# inverter.net
KiCad netlist of a schematic drawn in EAGLE
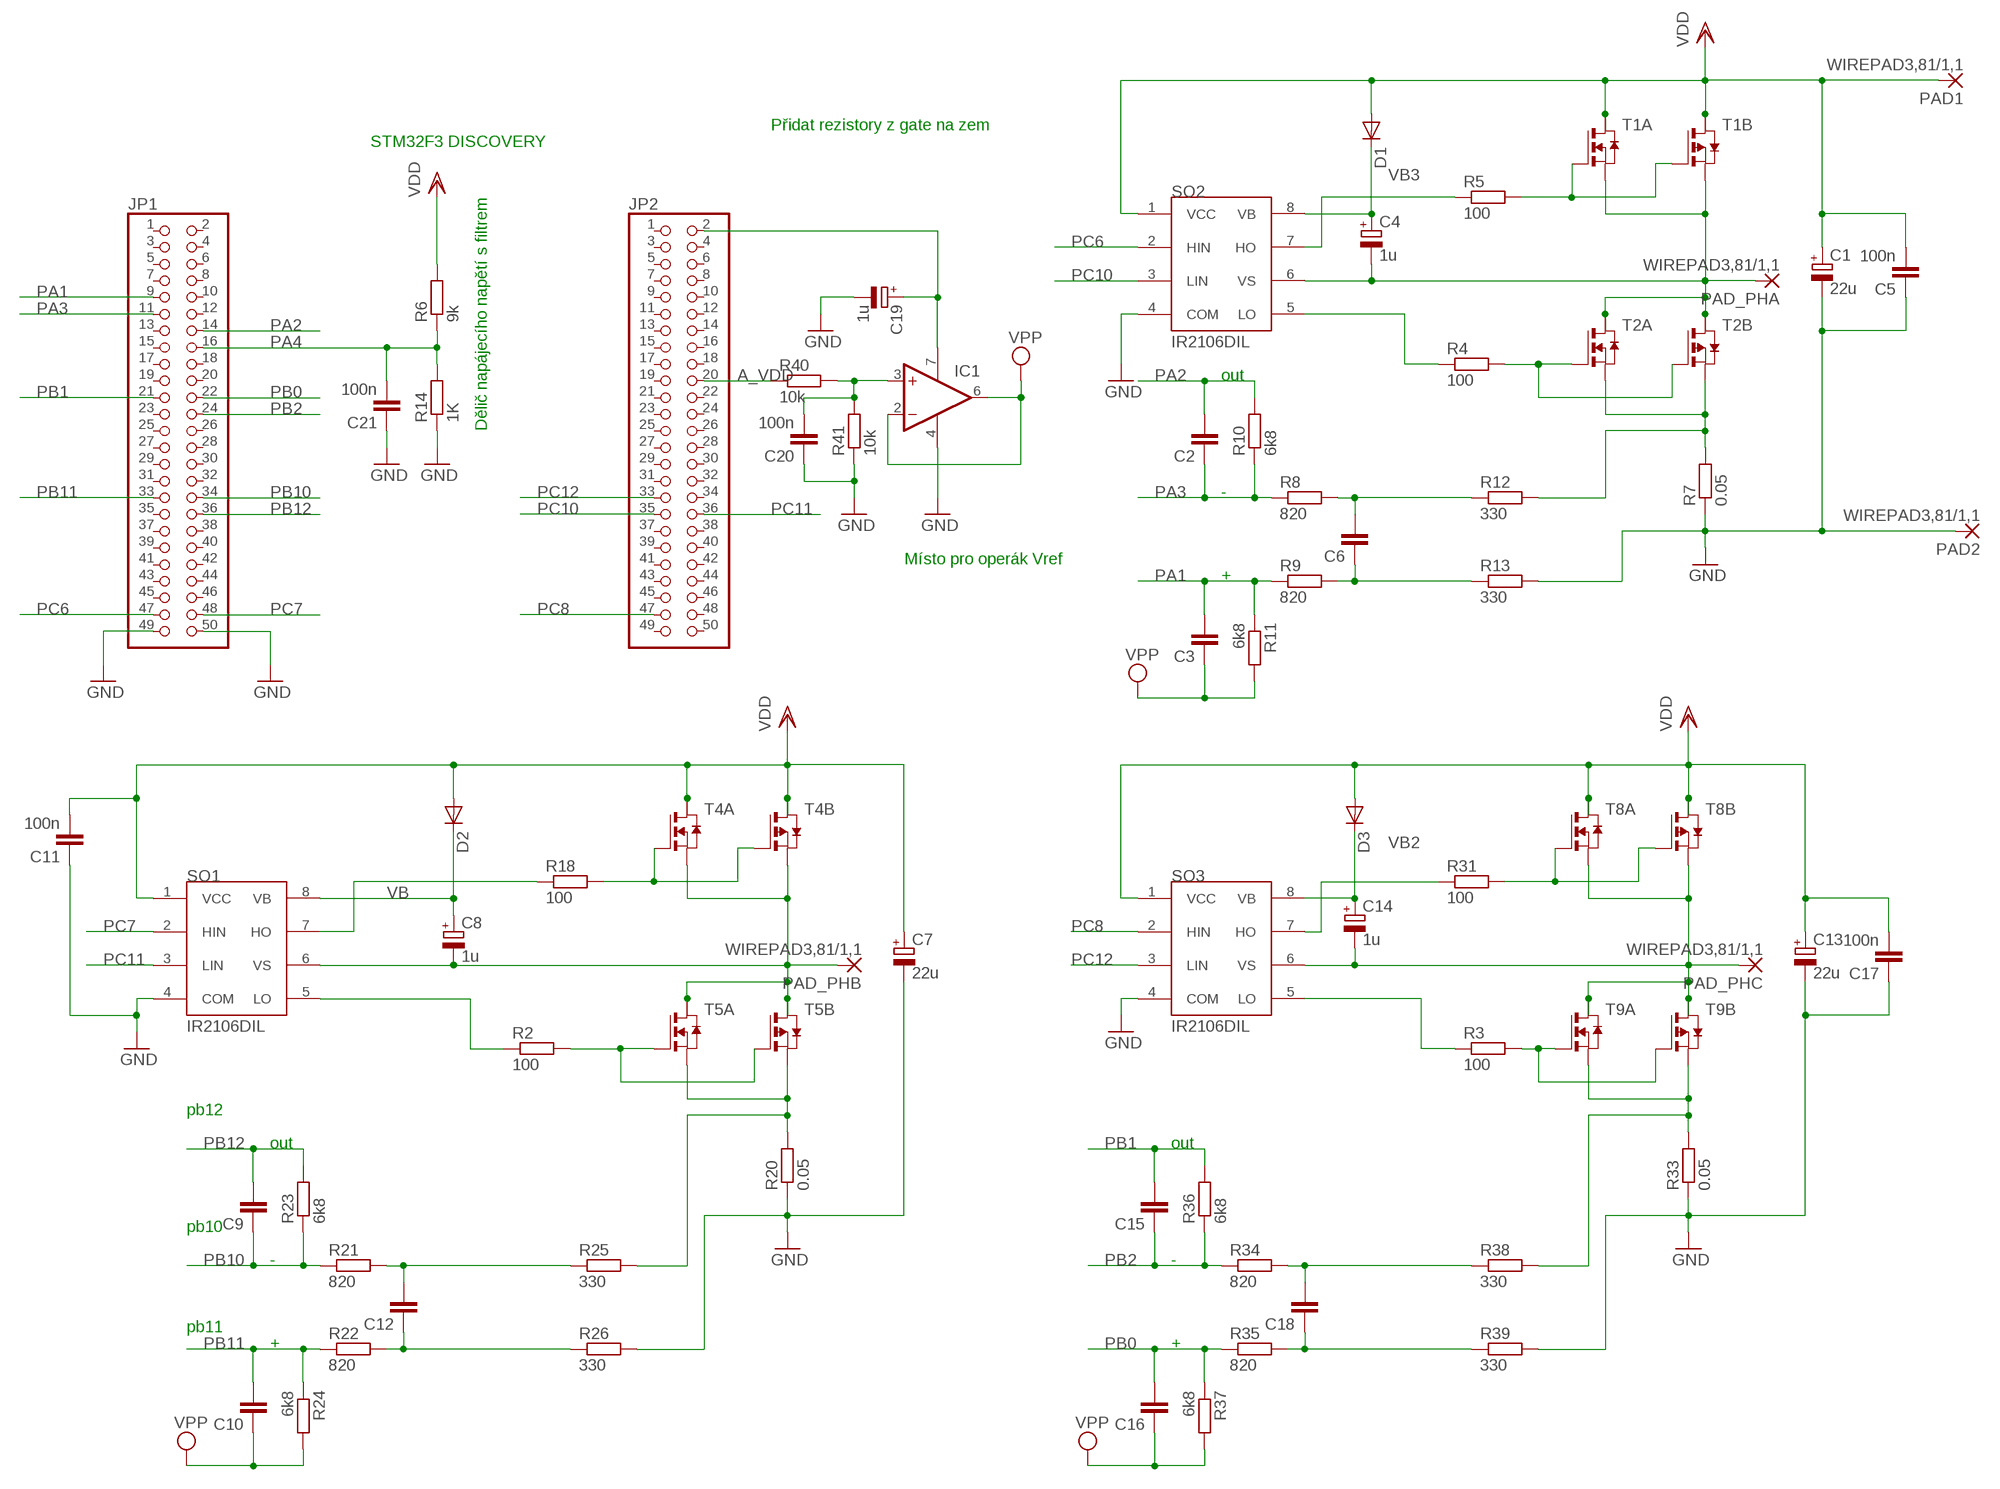
[diagram p0: schematic, sheet 1]

(export (version "E")
  (design (tool "Eeschema 10.0.6"))
  (components
    (comp (ref "C1")
      (value "22u")
      (footprint "eagle-import:SMC_C")
      (libsource (lib "eagle-import") (part "CPOL-EUSMCC"))
    )
    (comp (ref "C2")
      (value "C-EUC0805")
      (footprint "eagle-import:C0805")
      (libsource (lib "eagle-import") (part "C-EUC0805"))
    )
    (comp (ref "C3")
      (value "C-EUC0805")
      (footprint "eagle-import:C0805")
      (libsource (lib "eagle-import") (part "C-EUC0805"))
    )
    (comp (ref "C4")
      (value "1u")
      (footprint "eagle-import:SMC_P")
      (libsource (lib "eagle-import") (part "CPOL-EUSMCP"))
    )
    (comp (ref "C5")
      (value "100n")
      (footprint "eagle-import:C0805")
      (libsource (lib "eagle-import") (part "C-EUC0805"))
    )
    (comp (ref "C6")
      (value "C-EUC0805")
      (footprint "eagle-import:C0805")
      (libsource (lib "eagle-import") (part "C-EUC0805"))
    )
    (comp (ref "C7")
      (value "22u")
      (footprint "eagle-import:SMC_C")
      (libsource (lib "eagle-import") (part "CPOL-EUSMCC"))
    )
    (comp (ref "C8")
      (value "1u")
      (footprint "eagle-import:SMC_P")
      (libsource (lib "eagle-import") (part "CPOL-EUSMCP"))
    )
    (comp (ref "C9")
      (value "C-EUC0805")
      (footprint "eagle-import:C0805")
      (libsource (lib "eagle-import") (part "C-EUC0805"))
    )
    (comp (ref "C10")
      (value "C-EUC0805")
      (footprint "eagle-import:C0805")
      (libsource (lib "eagle-import") (part "C-EUC0805"))
    )
    (comp (ref "C11")
      (value "100n")
      (footprint "eagle-import:C0805")
      (libsource (lib "eagle-import") (part "C-EUC0805"))
    )
    (comp (ref "C12")
      (value "C-EUC0805")
      (footprint "eagle-import:C0805")
      (libsource (lib "eagle-import") (part "C-EUC0805"))
    )
    (comp (ref "C13")
      (value "22u")
      (footprint "eagle-import:SMC_C")
      (libsource (lib "eagle-import") (part "CPOL-EUSMCC"))
    )
    (comp (ref "C14")
      (value "1u")
      (footprint "eagle-import:SMC_P")
      (libsource (lib "eagle-import") (part "CPOL-EUSMCP"))
    )
    (comp (ref "C15")
      (value "C-EUC0805")
      (footprint "eagle-import:C0805")
      (libsource (lib "eagle-import") (part "C-EUC0805"))
    )
    (comp (ref "C16")
      (value "C-EUC0805")
      (footprint "eagle-import:C0805")
      (libsource (lib "eagle-import") (part "C-EUC0805"))
    )
    (comp (ref "C17")
      (value "100n")
      (footprint "eagle-import:C0805")
      (libsource (lib "eagle-import") (part "C-EUC0805"))
    )
    (comp (ref "C18")
      (value "C-EUC0805")
      (footprint "eagle-import:C0805")
      (libsource (lib "eagle-import") (part "C-EUC0805"))
    )
    (comp (ref "C19")
      (value "1u")
      (footprint "eagle-import:SMC_P")
      (libsource (lib "eagle-import") (part "CPOL-EUSMCP"))
    )
    (comp (ref "C20")
      (value "100n")
      (footprint "eagle-import:C0805")
      (libsource (lib "eagle-import") (part "C-EUC0805"))
    )
    (comp (ref "C21")
      (value "100n")
      (footprint "eagle-import:C0805")
      (libsource (lib "eagle-import") (part "C-EUC0805"))
    )
    (comp (ref "D1")
      (value "DIODE-DO214AC")
      (footprint "eagle-import:DO214AC")
      (libsource (lib "eagle-import") (part "DIODE-DO214AC"))
    )
    (comp (ref "D2")
      (value "DIODE-DO214AC")
      (footprint "eagle-import:DO214AC")
      (libsource (lib "eagle-import") (part "DIODE-DO214AC"))
    )
    (comp (ref "D3")
      (value "DIODE-DO214AC")
      (footprint "eagle-import:DO214AC")
      (libsource (lib "eagle-import") (part "DIODE-DO214AC"))
    )
    (comp (ref "IC1")
      (value "1AMP_P7+4D")
      (footprint "eagle-import:SO08")
      (libsource (lib "eagle-import") (part "1AMP_P7+4D"))
    )
    (comp (ref "JP1")
      (value "PINHD-2X25")
      (footprint "eagle-import:2X25")
      (libsource (lib "eagle-import") (part "PINHD-2X25"))
    )
    (comp (ref "JP2")
      (value "PINHD-2X25")
      (footprint "eagle-import:2X25")
      (libsource (lib "eagle-import") (part "PINHD-2X25"))
    )
    (comp (ref "PAD1")
      (value "WIREPAD3,81/1,1")
      (footprint "eagle-import:3,81_1,1")
      (libsource (lib "eagle-import") (part "WIREPAD3,81/1,1"))
    )
    (comp (ref "PAD2")
      (value "WIREPAD3,81/1,1")
      (footprint "eagle-import:3,81_1,1")
      (libsource (lib "eagle-import") (part "WIREPAD3,81/1,1"))
    )
    (comp (ref "PAD_PHA")
      (value "WIREPAD3,81/1,1")
      (footprint "eagle-import:3,81_1,1")
      (libsource (lib "eagle-import") (part "WIREPAD3,81/1,1"))
    )
    (comp (ref "PAD_PHB")
      (value "WIREPAD3,81/1,1")
      (footprint "eagle-import:3,81_1,1")
      (libsource (lib "eagle-import") (part "WIREPAD3,81/1,1"))
    )
    (comp (ref "PAD_PHC")
      (value "WIREPAD3,81/1,1")
      (footprint "eagle-import:3,81_1,1")
      (libsource (lib "eagle-import") (part "WIREPAD3,81/1,1"))
    )
    (comp (ref "R2")
      (value "100")
      (footprint "eagle-import:M1206")
      (libsource (lib "eagle-import") (part "R-EU_M1206"))
    )
    (comp (ref "R3")
      (value "100")
      (footprint "eagle-import:M1206")
      (libsource (lib "eagle-import") (part "R-EU_M1206"))
    )
    (comp (ref "R4")
      (value "100")
      (footprint "eagle-import:M1206")
      (libsource (lib "eagle-import") (part "R-EU_M1206"))
    )
    (comp (ref "R5")
      (value "100")
      (footprint "eagle-import:M1206")
      (libsource (lib "eagle-import") (part "R-EU_M1206"))
    )
    (comp (ref "R6")
      (value "9k")
      (footprint "eagle-import:M1206")
      (libsource (lib "eagle-import") (part "R-EU_M1206"))
    )
    (comp (ref "R7")
      (value "0.05")
      (footprint "eagle-import:R2512")
      (libsource (lib "eagle-import") (part "R-EU_R2512"))
    )
    (comp (ref "R8")
      (value "820")
      (footprint "eagle-import:M1206")
      (libsource (lib "eagle-import") (part "R-EU_M1206"))
    )
    (comp (ref "R9")
      (value "820")
      (footprint "eagle-import:M1206")
      (libsource (lib "eagle-import") (part "R-EU_M1206"))
    )
    (comp (ref "R10")
      (value "6k8")
      (footprint "eagle-import:M1206")
      (libsource (lib "eagle-import") (part "R-EU_M1206"))
    )
    (comp (ref "R11")
      (value "6k8")
      (footprint "eagle-import:M1206")
      (libsource (lib "eagle-import") (part "R-EU_M1206"))
    )
    (comp (ref "R12")
      (value "330")
      (footprint "eagle-import:M1206")
      (libsource (lib "eagle-import") (part "R-EU_M1206"))
    )
    (comp (ref "R13")
      (value "330")
      (footprint "eagle-import:M1206")
      (libsource (lib "eagle-import") (part "R-EU_M1206"))
    )
    (comp (ref "R14")
      (value "1K")
      (footprint "eagle-import:M1206")
      (libsource (lib "eagle-import") (part "R-EU_M1206"))
    )
    (comp (ref "R18")
      (value "100")
      (footprint "eagle-import:M1206")
      (libsource (lib "eagle-import") (part "R-EU_M1206"))
    )
    (comp (ref "R20")
      (value "0.05")
      (footprint "eagle-import:R2512")
      (libsource (lib "eagle-import") (part "R-EU_R2512"))
    )
    (comp (ref "R21")
      (value "820")
      (footprint "eagle-import:M1206")
      (libsource (lib "eagle-import") (part "R-EU_M1206"))
    )
    (comp (ref "R22")
      (value "820")
      (footprint "eagle-import:M1206")
      (libsource (lib "eagle-import") (part "R-EU_M1206"))
    )
    (comp (ref "R23")
      (value "6k8")
      (footprint "eagle-import:M1206")
      (libsource (lib "eagle-import") (part "R-EU_M1206"))
    )
    (comp (ref "R24")
      (value "6k8")
      (footprint "eagle-import:M1206")
      (libsource (lib "eagle-import") (part "R-EU_M1206"))
    )
    (comp (ref "R25")
      (value "330")
      (footprint "eagle-import:M1206")
      (libsource (lib "eagle-import") (part "R-EU_M1206"))
    )
    (comp (ref "R26")
      (value "330")
      (footprint "eagle-import:M1206")
      (libsource (lib "eagle-import") (part "R-EU_M1206"))
    )
    (comp (ref "R31")
      (value "100")
      (footprint "eagle-import:M1206")
      (libsource (lib "eagle-import") (part "R-EU_M1206"))
    )
    (comp (ref "R33")
      (value "0.05")
      (footprint "eagle-import:R2512")
      (libsource (lib "eagle-import") (part "R-EU_R2512"))
    )
    (comp (ref "R34")
      (value "820")
      (footprint "eagle-import:M1206")
      (libsource (lib "eagle-import") (part "R-EU_M1206"))
    )
    (comp (ref "R35")
      (value "820")
      (footprint "eagle-import:M1206")
      (libsource (lib "eagle-import") (part "R-EU_M1206"))
    )
    (comp (ref "R36")
      (value "6k8")
      (footprint "eagle-import:M1206")
      (libsource (lib "eagle-import") (part "R-EU_M1206"))
    )
    (comp (ref "R37")
      (value "6k8")
      (footprint "eagle-import:M1206")
      (libsource (lib "eagle-import") (part "R-EU_M1206"))
    )
    (comp (ref "R38")
      (value "330")
      (footprint "eagle-import:M1206")
      (libsource (lib "eagle-import") (part "R-EU_M1206"))
    )
    (comp (ref "R39")
      (value "330")
      (footprint "eagle-import:M1206")
      (libsource (lib "eagle-import") (part "R-EU_M1206"))
    )
    (comp (ref "R40")
      (value "10k")
      (footprint "eagle-import:M1206")
      (libsource (lib "eagle-import") (part "R-EU_M1206"))
    )
    (comp (ref "R41")
      (value "10k")
      (footprint "eagle-import:M1206")
      (libsource (lib "eagle-import") (part "R-EU_M1206"))
    )
    (comp (ref "SO1")
      (value "IR2106DIL")
      (footprint "eagle-import:SO8")
      (libsource (lib "eagle-import") (part "IR2106DIL"))
    )
    (comp (ref "SO2")
      (value "IR2106DIL")
      (footprint "eagle-import:SO8")
      (libsource (lib "eagle-import") (part "IR2106DIL"))
    )
    (comp (ref "SO3")
      (value "IR2106DIL")
      (footprint "eagle-import:SO8")
      (libsource (lib "eagle-import") (part "IR2106DIL"))
    )
    (comp (ref "T1")
      (value "PN_MOSFET-SO8")
      (footprint "eagle-import:SO8")
      (libsource (lib "eagle-import") (part "PN_MOSFET-SO8"))
    )
    (comp (ref "T2")
      (value "PN_MOSFET-SO8")
      (footprint "eagle-import:SO8")
      (libsource (lib "eagle-import") (part "PN_MOSFET-SO8"))
    )
    (comp (ref "T4")
      (value "PN_MOSFET-SO8")
      (footprint "eagle-import:SO8")
      (libsource (lib "eagle-import") (part "PN_MOSFET-SO8"))
    )
    (comp (ref "T5")
      (value "PN_MOSFET-SO8")
      (footprint "eagle-import:SO8")
      (libsource (lib "eagle-import") (part "PN_MOSFET-SO8"))
    )
    (comp (ref "T8")
      (value "PN_MOSFET-SO8")
      (footprint "eagle-import:SO8")
      (libsource (lib "eagle-import") (part "PN_MOSFET-SO8"))
    )
    (comp (ref "T9")
      (value "PN_MOSFET-SO8")
      (footprint "eagle-import:SO8")
      (libsource (lib "eagle-import") (part "PN_MOSFET-SO8"))
    )
  )
  (nets
    (net (code "1") (name "/A_VDD") (class "Default")
      (node (ref "JP2") (pin "20") (pinfunction "20_20") (pintype "passive"))
      (node (ref "R40") (pin "1") (pinfunction "1_1") (pintype "passive"))
    )
    (net (code "2") (name "/PA1") (class "Default")
      (node (ref "C3") (pin "2") (pinfunction "2_2") (pintype "passive"))
      (node (ref "JP1") (pin "9") (pinfunction "9_9") (pintype "passive"))
      (node (ref "R11") (pin "1") (pinfunction "1_1") (pintype "passive"))
      (node (ref "R9") (pin "1") (pinfunction "1_1") (pintype "passive"))
    )
    (net (code "3") (name "/PA2") (class "Default")
      (node (ref "C2") (pin "2") (pinfunction "2_2") (pintype "passive"))
      (node (ref "JP1") (pin "14") (pinfunction "14_14") (pintype "passive"))
      (node (ref "R10") (pin "2") (pinfunction "2_2") (pintype "passive"))
    )
    (net (code "4") (name "/PA3") (class "Default")
      (node (ref "C2") (pin "1") (pinfunction "1_1") (pintype "passive"))
      (node (ref "JP1") (pin "11") (pinfunction "11_11") (pintype "passive"))
      (node (ref "R10") (pin "1") (pinfunction "1_1") (pintype "passive"))
      (node (ref "R8") (pin "1") (pinfunction "1_1") (pintype "passive"))
    )
    (net (code "5") (name "/PA4") (class "Default")
      (node (ref "C21") (pin "2") (pinfunction "2_2") (pintype "passive"))
      (node (ref "JP1") (pin "16") (pinfunction "16_16") (pintype "passive"))
      (node (ref "R14") (pin "2") (pinfunction "2_2") (pintype "passive"))
      (node (ref "R6") (pin "1") (pinfunction "1_1") (pintype "passive"))
    )
    (net (code "6") (name "/PB0") (class "Default")
      (node (ref "C16") (pin "2") (pinfunction "2_2") (pintype "passive"))
      (node (ref "JP1") (pin "22") (pinfunction "22_22") (pintype "passive"))
      (node (ref "R35") (pin "1") (pinfunction "1_1") (pintype "passive"))
      (node (ref "R37") (pin "1") (pinfunction "1_1") (pintype "passive"))
    )
    (net (code "7") (name "/PB1") (class "Default")
      (node (ref "C15") (pin "2") (pinfunction "2_2") (pintype "passive"))
      (node (ref "JP1") (pin "21") (pinfunction "21_21") (pintype "passive"))
      (node (ref "R36") (pin "2") (pinfunction "2_2") (pintype "passive"))
    )
    (net (code "8") (name "/PB2") (class "Default")
      (node (ref "C15") (pin "1") (pinfunction "1_1") (pintype "passive"))
      (node (ref "JP1") (pin "24") (pinfunction "24_24") (pintype "passive"))
      (node (ref "R34") (pin "1") (pinfunction "1_1") (pintype "passive"))
      (node (ref "R36") (pin "1") (pinfunction "1_1") (pintype "passive"))
    )
    (net (code "9") (name "/PB10") (class "Default")
      (node (ref "C9") (pin "1") (pinfunction "1_1") (pintype "passive"))
      (node (ref "JP1") (pin "34") (pinfunction "34_34") (pintype "passive"))
      (node (ref "R21") (pin "1") (pinfunction "1_1") (pintype "passive"))
      (node (ref "R23") (pin "1") (pinfunction "1_1") (pintype "passive"))
    )
    (net (code "10") (name "/PB11") (class "Default")
      (node (ref "C10") (pin "2") (pinfunction "2_2") (pintype "passive"))
      (node (ref "JP1") (pin "33") (pinfunction "33_33") (pintype "passive"))
      (node (ref "R22") (pin "1") (pinfunction "1_1") (pintype "passive"))
      (node (ref "R24") (pin "1") (pinfunction "1_1") (pintype "passive"))
    )
    (net (code "11") (name "/PB12") (class "Default")
      (node (ref "C9") (pin "2") (pinfunction "2_2") (pintype "passive"))
      (node (ref "JP1") (pin "36") (pinfunction "36_36") (pintype "passive"))
      (node (ref "R23") (pin "2") (pinfunction "2_2") (pintype "passive"))
    )
    (net (code "12") (name "/PC6") (class "Default")
      (node (ref "JP1") (pin "47") (pinfunction "47_47") (pintype "passive"))
      (node (ref "SO2") (pin "2") (pinfunction "HIN_2") (pintype "input"))
    )
    (net (code "13") (name "/PC7") (class "Default")
      (node (ref "JP1") (pin "48") (pinfunction "48_48") (pintype "passive"))
      (node (ref "SO1") (pin "2") (pinfunction "HIN_2") (pintype "input"))
    )
    (net (code "14") (name "/PC8") (class "Default")
      (node (ref "JP2") (pin "47") (pinfunction "47_47") (pintype "passive"))
      (node (ref "SO3") (pin "2") (pinfunction "HIN_2") (pintype "input"))
    )
    (net (code "15") (name "/PC10") (class "Default")
      (node (ref "JP2") (pin "35") (pinfunction "35_35") (pintype "passive"))
      (node (ref "SO2") (pin "3") (pinfunction "LIN_3") (pintype "input"))
    )
    (net (code "16") (name "/PC11") (class "Default")
      (node (ref "JP2") (pin "36") (pinfunction "36_36") (pintype "passive"))
      (node (ref "SO1") (pin "3") (pinfunction "LIN_3") (pintype "input"))
    )
    (net (code "17") (name "/PC12") (class "Default")
      (node (ref "JP2") (pin "33") (pinfunction "33_33") (pintype "passive"))
      (node (ref "SO3") (pin "3") (pinfunction "LIN_3") (pintype "input"))
    )
    (net (code "18") (name "/VB") (class "Default")
      (node (ref "C8") (pin "+") (pinfunction "+_+") (pintype "passive"))
      (node (ref "D2") (pin "C") (pinfunction "C_C") (pintype "passive"))
      (node (ref "SO1") (pin "8") (pinfunction "VB_8") (pintype "power_in"))
    )
    (net (code "19") (name "/VB2") (class "Default")
      (node (ref "C14") (pin "+") (pinfunction "+_+") (pintype "passive"))
      (node (ref "D3") (pin "C") (pinfunction "C_C") (pintype "passive"))
      (node (ref "SO3") (pin "8") (pinfunction "VB_8") (pintype "power_in"))
    )
    (net (code "20") (name "/VB3") (class "Default")
      (node (ref "C4") (pin "+") (pinfunction "+_+") (pintype "passive"))
      (node (ref "D1") (pin "C") (pinfunction "C_C") (pintype "passive"))
      (node (ref "SO2") (pin "8") (pinfunction "VB_8") (pintype "power_in"))
    )
    (net (code "21") (name "GND") (class "Default")
      (node (ref "C1") (pin "-") (pinfunction "-_-") (pintype "passive"))
      (node (ref "C11") (pin "1") (pinfunction "1_1") (pintype "passive"))
      (node (ref "C13") (pin "-") (pinfunction "-_-") (pintype "passive"))
      (node (ref "C17") (pin "1") (pinfunction "1_1") (pintype "passive"))
      (node (ref "C19") (pin "-") (pinfunction "-_-") (pintype "passive"))
      (node (ref "C20") (pin "1") (pinfunction "1_1") (pintype "passive"))
      (node (ref "C21") (pin "1") (pinfunction "1_1") (pintype "passive"))
      (node (ref "C5") (pin "1") (pinfunction "1_1") (pintype "passive"))
      (node (ref "C7") (pin "-") (pinfunction "-_-") (pintype "passive"))
      (node (ref "IC1") (pin "4") (pinfunction "V-_4") (pintype "power_in"))
      (node (ref "JP1") (pin "49") (pinfunction "49_49") (pintype "passive"))
      (node (ref "JP1") (pin "50") (pinfunction "50_50") (pintype "passive"))
      (node (ref "PAD2") (pin "1") (pinfunction "P_1") (pintype "passive"))
      (node (ref "R13") (pin "2") (pinfunction "2_2") (pintype "passive"))
      (node (ref "R14") (pin "1") (pinfunction "1_1") (pintype "passive"))
      (node (ref "R20") (pin "1") (pinfunction "1_1") (pintype "passive"))
      (node (ref "R26") (pin "2") (pinfunction "2_2") (pintype "passive"))
      (node (ref "R33") (pin "1") (pinfunction "1_1") (pintype "passive"))
      (node (ref "R39") (pin "2") (pinfunction "2_2") (pintype "passive"))
      (node (ref "R41") (pin "1") (pinfunction "1_1") (pintype "passive"))
      (node (ref "R7") (pin "1") (pinfunction "1_1") (pintype "passive"))
      (node (ref "SO1") (pin "4") (pinfunction "COM_4") (pintype "power_in"))
      (node (ref "SO2") (pin "4") (pinfunction "COM_4") (pintype "power_in"))
      (node (ref "SO3") (pin "4") (pinfunction "COM_4") (pintype "power_in"))
    )
    (net (code "22") (name "Net-(C6-Pad1)") (class "Default")
      (node (ref "C6") (pin "1") (pinfunction "1_1") (pintype "passive"))
      (node (ref "R13") (pin "1") (pinfunction "1_1") (pintype "passive"))
      (node (ref "R9") (pin "2") (pinfunction "2_2") (pintype "passive"))
    )
    (net (code "23") (name "Net-(C6-Pad2)") (class "Default")
      (node (ref "C6") (pin "2") (pinfunction "2_2") (pintype "passive"))
      (node (ref "R12") (pin "1") (pinfunction "1_1") (pintype "passive"))
      (node (ref "R8") (pin "2") (pinfunction "2_2") (pintype "passive"))
    )
    (net (code "24") (name "Net-(C12-Pad1)") (class "Default")
      (node (ref "C12") (pin "1") (pinfunction "1_1") (pintype "passive"))
      (node (ref "R22") (pin "2") (pinfunction "2_2") (pintype "passive"))
      (node (ref "R26") (pin "1") (pinfunction "1_1") (pintype "passive"))
    )
    (net (code "25") (name "Net-(C12-Pad2)") (class "Default")
      (node (ref "C12") (pin "2") (pinfunction "2_2") (pintype "passive"))
      (node (ref "R21") (pin "2") (pinfunction "2_2") (pintype "passive"))
      (node (ref "R25") (pin "1") (pinfunction "1_1") (pintype "passive"))
    )
    (net (code "26") (name "Net-(C18-Pad1)") (class "Default")
      (node (ref "C18") (pin "1") (pinfunction "1_1") (pintype "passive"))
      (node (ref "R35") (pin "2") (pinfunction "2_2") (pintype "passive"))
      (node (ref "R39") (pin "1") (pinfunction "1_1") (pintype "passive"))
    )
    (net (code "27") (name "Net-(C18-Pad2)") (class "Default")
      (node (ref "C18") (pin "2") (pinfunction "2_2") (pintype "passive"))
      (node (ref "R34") (pin "2") (pinfunction "2_2") (pintype "passive"))
      (node (ref "R38") (pin "1") (pinfunction "1_1") (pintype "passive"))
    )
    (net (code "28") (name "Net-(IC1-+IN)") (class "Default")
      (node (ref "C20") (pin "2") (pinfunction "2_2") (pintype "passive"))
      (node (ref "IC1") (pin "3") (pinfunction "+IN_3") (pintype "input"))
      (node (ref "R40") (pin "2") (pinfunction "2_2") (pintype "passive"))
      (node (ref "R41") (pin "2") (pinfunction "2_2") (pintype "passive"))
    )
    (net (code "29") (name "Net-(IC1-V+)") (class "Default")
      (node (ref "C19") (pin "+") (pinfunction "+_+") (pintype "passive"))
      (node (ref "IC1") (pin "7") (pinfunction "V+_7") (pintype "power_in"))
      (node (ref "JP2") (pin "2") (pinfunction "2_2") (pintype "passive"))
    )
    (net (code "30") (name "Net-(PAD_PHA-P)") (class "Default")
      (node (ref "C4") (pin "-") (pinfunction "-_-") (pintype "passive"))
      (node (ref "PAD_PHA") (pin "1") (pinfunction "P_1") (pintype "passive"))
      (node (ref "SO2") (pin "6") (pinfunction "VS_6") (pintype "output"))
      (node (ref "T1") (pin "1") (pinfunction "S_1") (pintype "passive"))
      (node (ref "T1") (pin "3") (pinfunction "S_3") (pintype "passive"))
      (node (ref "T2") (pin "5") (pinfunction "D_5") (pintype "passive"))
      (node (ref "T2") (pin "6") (pinfunction "D2_6") (pintype "passive"))
      (node (ref "T2") (pin "7") (pinfunction "D_7") (pintype "passive"))
      (node (ref "T2") (pin "8") (pinfunction "D2_8") (pintype "passive"))
    )
    (net (code "31") (name "Net-(PAD_PHB-P)") (class "Default")
      (node (ref "C8") (pin "-") (pinfunction "-_-") (pintype "passive"))
      (node (ref "PAD_PHB") (pin "1") (pinfunction "P_1") (pintype "passive"))
      (node (ref "SO1") (pin "6") (pinfunction "VS_6") (pintype "output"))
      (node (ref "T4") (pin "1") (pinfunction "S_1") (pintype "passive"))
      (node (ref "T4") (pin "3") (pinfunction "S_3") (pintype "passive"))
      (node (ref "T5") (pin "5") (pinfunction "D_5") (pintype "passive"))
      (node (ref "T5") (pin "6") (pinfunction "D2_6") (pintype "passive"))
      (node (ref "T5") (pin "7") (pinfunction "D_7") (pintype "passive"))
      (node (ref "T5") (pin "8") (pinfunction "D2_8") (pintype "passive"))
    )
    (net (code "32") (name "Net-(PAD_PHC-P)") (class "Default")
      (node (ref "C14") (pin "-") (pinfunction "-_-") (pintype "passive"))
      (node (ref "PAD_PHC") (pin "1") (pinfunction "P_1") (pintype "passive"))
      (node (ref "SO3") (pin "6") (pinfunction "VS_6") (pintype "output"))
      (node (ref "T8") (pin "1") (pinfunction "S_1") (pintype "passive"))
      (node (ref "T8") (pin "3") (pinfunction "S_3") (pintype "passive"))
      (node (ref "T9") (pin "5") (pinfunction "D_5") (pintype "passive"))
      (node (ref "T9") (pin "6") (pinfunction "D2_6") (pintype "passive"))
      (node (ref "T9") (pin "7") (pinfunction "D_7") (pintype "passive"))
      (node (ref "T9") (pin "8") (pinfunction "D2_8") (pintype "passive"))
    )
    (net (code "33") (name "Net-(SO1-HO)") (class "Default")
      (node (ref "R18") (pin "1") (pinfunction "1_1") (pintype "passive"))
      (node (ref "SO1") (pin "7") (pinfunction "HO_7") (pintype "output"))
    )
    (net (code "34") (name "Net-(SO1-LO)") (class "Default")
      (node (ref "R2") (pin "1") (pinfunction "1_1") (pintype "passive"))
      (node (ref "SO1") (pin "5") (pinfunction "LO_5") (pintype "output"))
    )
    (net (code "35") (name "Net-(SO2-HO)") (class "Default")
      (node (ref "R5") (pin "1") (pinfunction "1_1") (pintype "passive"))
      (node (ref "SO2") (pin "7") (pinfunction "HO_7") (pintype "output"))
    )
    (net (code "36") (name "Net-(SO2-LO)") (class "Default")
      (node (ref "R4") (pin "1") (pinfunction "1_1") (pintype "passive"))
      (node (ref "SO2") (pin "5") (pinfunction "LO_5") (pintype "output"))
    )
    (net (code "37") (name "Net-(SO3-HO)") (class "Default")
      (node (ref "R31") (pin "1") (pinfunction "1_1") (pintype "passive"))
      (node (ref "SO3") (pin "7") (pinfunction "HO_7") (pintype "output"))
    )
    (net (code "38") (name "Net-(SO3-LO)") (class "Default")
      (node (ref "R3") (pin "1") (pinfunction "1_1") (pintype "passive"))
      (node (ref "SO3") (pin "5") (pinfunction "LO_5") (pintype "output"))
    )
    (net (code "39") (name "Net-(T1A-G)") (class "Default")
      (node (ref "R5") (pin "2") (pinfunction "2_2") (pintype "passive"))
      (node (ref "T1") (pin "2") (pinfunction "G_2") (pintype "passive"))
      (node (ref "T1") (pin "4") (pinfunction "G_4") (pintype "passive"))
    )
    (net (code "40") (name "Net-(T2A-G)") (class "Default")
      (node (ref "R4") (pin "2") (pinfunction "2_2") (pintype "passive"))
      (node (ref "T2") (pin "2") (pinfunction "G_2") (pintype "passive"))
      (node (ref "T2") (pin "4") (pinfunction "G_4") (pintype "passive"))
    )
    (net (code "41") (name "Net-(T2A-S)") (class "Default")
      (node (ref "R12") (pin "2") (pinfunction "2_2") (pintype "passive"))
      (node (ref "R7") (pin "2") (pinfunction "2_2") (pintype "passive"))
      (node (ref "T2") (pin "1") (pinfunction "S_1") (pintype "passive"))
      (node (ref "T2") (pin "3") (pinfunction "S_3") (pintype "passive"))
    )
    (net (code "42") (name "Net-(T4A-G)") (class "Default")
      (node (ref "R18") (pin "2") (pinfunction "2_2") (pintype "passive"))
      (node (ref "T4") (pin "2") (pinfunction "G_2") (pintype "passive"))
      (node (ref "T4") (pin "4") (pinfunction "G_4") (pintype "passive"))
    )
    (net (code "43") (name "Net-(T5A-G)") (class "Default")
      (node (ref "R2") (pin "2") (pinfunction "2_2") (pintype "passive"))
      (node (ref "T5") (pin "2") (pinfunction "G_2") (pintype "passive"))
      (node (ref "T5") (pin "4") (pinfunction "G_4") (pintype "passive"))
    )
    (net (code "44") (name "Net-(T5A-S)") (class "Default")
      (node (ref "R20") (pin "2") (pinfunction "2_2") (pintype "passive"))
      (node (ref "R25") (pin "2") (pinfunction "2_2") (pintype "passive"))
      (node (ref "T5") (pin "1") (pinfunction "S_1") (pintype "passive"))
      (node (ref "T5") (pin "3") (pinfunction "S_3") (pintype "passive"))
    )
    (net (code "45") (name "Net-(T8A-G)") (class "Default")
      (node (ref "R31") (pin "2") (pinfunction "2_2") (pintype "passive"))
      (node (ref "T8") (pin "2") (pinfunction "G_2") (pintype "passive"))
      (node (ref "T8") (pin "4") (pinfunction "G_4") (pintype "passive"))
    )
    (net (code "46") (name "Net-(T9A-G)") (class "Default")
      (node (ref "R3") (pin "2") (pinfunction "2_2") (pintype "passive"))
      (node (ref "T9") (pin "2") (pinfunction "G_2") (pintype "passive"))
      (node (ref "T9") (pin "4") (pinfunction "G_4") (pintype "passive"))
    )
    (net (code "47") (name "Net-(T9A-S)") (class "Default")
      (node (ref "R33") (pin "2") (pinfunction "2_2") (pintype "passive"))
      (node (ref "R38") (pin "2") (pinfunction "2_2") (pintype "passive"))
      (node (ref "T9") (pin "1") (pinfunction "S_1") (pintype "passive"))
      (node (ref "T9") (pin "3") (pinfunction "S_3") (pintype "passive"))
    )
    (net (code "48") (name "VDD") (class "Default")
      (node (ref "C1") (pin "+") (pinfunction "+_+") (pintype "passive"))
      (node (ref "C11") (pin "2") (pinfunction "2_2") (pintype "passive"))
      (node (ref "C13") (pin "+") (pinfunction "+_+") (pintype "passive"))
      (node (ref "C17") (pin "2") (pinfunction "2_2") (pintype "passive"))
      (node (ref "C5") (pin "2") (pinfunction "2_2") (pintype "passive"))
      (node (ref "C7") (pin "+") (pinfunction "+_+") (pintype "passive"))
      (node (ref "D1") (pin "A") (pinfunction "A_A") (pintype "passive"))
      (node (ref "D2") (pin "A") (pinfunction "A_A") (pintype "passive"))
      (node (ref "D3") (pin "A") (pinfunction "A_A") (pintype "passive"))
      (node (ref "PAD1") (pin "1") (pinfunction "P_1") (pintype "passive"))
      (node (ref "R6") (pin "2") (pinfunction "2_2") (pintype "passive"))
      (node (ref "SO1") (pin "1") (pinfunction "VCC_1") (pintype "power_in"))
      (node (ref "SO2") (pin "1") (pinfunction "VCC_1") (pintype "power_in"))
      (node (ref "SO3") (pin "1") (pinfunction "VCC_1") (pintype "power_in"))
      (node (ref "T1") (pin "5") (pinfunction "D_5") (pintype "passive"))
      (node (ref "T1") (pin "6") (pinfunction "D2_6") (pintype "passive"))
      (node (ref "T1") (pin "7") (pinfunction "D_7") (pintype "passive"))
      (node (ref "T1") (pin "8") (pinfunction "D2_8") (pintype "passive"))
      (node (ref "T4") (pin "5") (pinfunction "D_5") (pintype "passive"))
      (node (ref "T4") (pin "6") (pinfunction "D2_6") (pintype "passive"))
      (node (ref "T4") (pin "7") (pinfunction "D_7") (pintype "passive"))
      (node (ref "T4") (pin "8") (pinfunction "D2_8") (pintype "passive"))
      (node (ref "T8") (pin "5") (pinfunction "D_5") (pintype "passive"))
      (node (ref "T8") (pin "6") (pinfunction "D2_6") (pintype "passive"))
      (node (ref "T8") (pin "7") (pinfunction "D_7") (pintype "passive"))
      (node (ref "T8") (pin "8") (pinfunction "D2_8") (pintype "passive"))
    )
    (net (code "49") (name "VPP") (class "Default")
      (node (ref "C10") (pin "1") (pinfunction "1_1") (pintype "passive"))
      (node (ref "C16") (pin "1") (pinfunction "1_1") (pintype "passive"))
      (node (ref "C3") (pin "1") (pinfunction "1_1") (pintype "passive"))
      (node (ref "IC1") (pin "2") (pinfunction "-IN_2") (pintype "input"))
      (node (ref "IC1") (pin "6") (pinfunction "OUT_6") (pintype "output"))
      (node (ref "R11") (pin "2") (pinfunction "2_2") (pintype "passive"))
      (node (ref "R24") (pin "2") (pinfunction "2_2") (pintype "passive"))
      (node (ref "R37") (pin "2") (pinfunction "2_2") (pintype "passive"))
    )
    (net (code "50") (name "unconnected-(JP1-Pad1)") (class "Default")
      (node (ref "JP1") (pin "1") (pinfunction "1_1") (pintype "passive"))
    )
    (net (code "51") (name "unconnected-(JP1-Pad2)") (class "Default")
      (node (ref "JP1") (pin "2") (pinfunction "2_2") (pintype "passive"))
    )
    (net (code "52") (name "unconnected-(JP1-Pad3)") (class "Default")
      (node (ref "JP1") (pin "3") (pinfunction "3_3") (pintype "passive"))
    )
    (net (code "53") (name "unconnected-(JP1-Pad4)") (class "Default")
      (node (ref "JP1") (pin "4") (pinfunction "4_4") (pintype "passive"))
    )
    (net (code "54") (name "unconnected-(JP1-Pad5)") (class "Default")
      (node (ref "JP1") (pin "5") (pinfunction "5_5") (pintype "passive"))
    )
    (net (code "55") (name "unconnected-(JP1-Pad6)") (class "Default")
      (node (ref "JP1") (pin "6") (pinfunction "6_6") (pintype "passive"))
    )
    (net (code "56") (name "unconnected-(JP1-Pad7)") (class "Default")
      (node (ref "JP1") (pin "7") (pinfunction "7_7") (pintype "passive"))
    )
    (net (code "57") (name "unconnected-(JP1-Pad8)") (class "Default")
      (node (ref "JP1") (pin "8") (pinfunction "8_8") (pintype "passive"))
    )
    (net (code "58") (name "unconnected-(JP1-Pad10)") (class "Default")
      (node (ref "JP1") (pin "10") (pinfunction "10_10") (pintype "passive"))
    )
    (net (code "59") (name "unconnected-(JP1-Pad12)") (class "Default")
      (node (ref "JP1") (pin "12") (pinfunction "12_12") (pintype "passive"))
    )
    (net (code "60") (name "unconnected-(JP1-Pad13)") (class "Default")
      (node (ref "JP1") (pin "13") (pinfunction "13_13") (pintype "passive"))
    )
    (net (code "61") (name "unconnected-(JP1-Pad15)") (class "Default")
      (node (ref "JP1") (pin "15") (pinfunction "15_15") (pintype "passive"))
    )
    (net (code "62") (name "unconnected-(JP1-Pad17)") (class "Default")
      (node (ref "JP1") (pin "17") (pinfunction "17_17") (pintype "passive"))
    )
    (net (code "63") (name "unconnected-(JP1-Pad18)") (class "Default")
      (node (ref "JP1") (pin "18") (pinfunction "18_18") (pintype "passive"))
    )
    (net (code "64") (name "unconnected-(JP1-Pad19)") (class "Default")
      (node (ref "JP1") (pin "19") (pinfunction "19_19") (pintype "passive"))
    )
    (net (code "65") (name "unconnected-(JP1-Pad20)") (class "Default")
      (node (ref "JP1") (pin "20") (pinfunction "20_20") (pintype "passive"))
    )
    (net (code "66") (name "unconnected-(JP1-Pad23)") (class "Default")
      (node (ref "JP1") (pin "23") (pinfunction "23_23") (pintype "passive"))
    )
    (net (code "67") (name "unconnected-(JP1-Pad25)") (class "Default")
      (node (ref "JP1") (pin "25") (pinfunction "25_25") (pintype "passive"))
    )
    (net (code "68") (name "unconnected-(JP1-Pad26)") (class "Default")
      (node (ref "JP1") (pin "26") (pinfunction "26_26") (pintype "passive"))
    )
    (net (code "69") (name "unconnected-(JP1-Pad27)") (class "Default")
      (node (ref "JP1") (pin "27") (pinfunction "27_27") (pintype "passive"))
    )
    (net (code "70") (name "unconnected-(JP1-Pad28)") (class "Default")
      (node (ref "JP1") (pin "28") (pinfunction "28_28") (pintype "passive"))
    )
    (net (code "71") (name "unconnected-(JP1-Pad29)") (class "Default")
      (node (ref "JP1") (pin "29") (pinfunction "29_29") (pintype "passive"))
    )
    (net (code "72") (name "unconnected-(JP1-Pad30)") (class "Default")
      (node (ref "JP1") (pin "30") (pinfunction "30_30") (pintype "passive"))
    )
    (net (code "73") (name "unconnected-(JP1-Pad31)") (class "Default")
      (node (ref "JP1") (pin "31") (pinfunction "31_31") (pintype "passive"))
    )
    (net (code "74") (name "unconnected-(JP1-Pad32)") (class "Default")
      (node (ref "JP1") (pin "32") (pinfunction "32_32") (pintype "passive"))
    )
    (net (code "75") (name "unconnected-(JP1-Pad35)") (class "Default")
      (node (ref "JP1") (pin "35") (pinfunction "35_35") (pintype "passive"))
    )
    (net (code "76") (name "unconnected-(JP1-Pad37)") (class "Default")
      (node (ref "JP1") (pin "37") (pinfunction "37_37") (pintype "passive"))
    )
    (net (code "77") (name "unconnected-(JP1-Pad38)") (class "Default")
      (node (ref "JP1") (pin "38") (pinfunction "38_38") (pintype "passive"))
    )
    (net (code "78") (name "unconnected-(JP1-Pad39)") (class "Default")
      (node (ref "JP1") (pin "39") (pinfunction "39_39") (pintype "passive"))
    )
    (net (code "79") (name "unconnected-(JP1-Pad40)") (class "Default")
      (node (ref "JP1") (pin "40") (pinfunction "40_40") (pintype "passive"))
    )
    (net (code "80") (name "unconnected-(JP1-Pad41)") (class "Default")
      (node (ref "JP1") (pin "41") (pinfunction "41_41") (pintype "passive"))
    )
    (net (code "81") (name "unconnected-(JP1-Pad42)") (class "Default")
      (node (ref "JP1") (pin "42") (pinfunction "42_42") (pintype "passive"))
    )
    (net (code "82") (name "unconnected-(JP1-Pad43)") (class "Default")
      (node (ref "JP1") (pin "43") (pinfunction "43_43") (pintype "passive"))
    )
    (net (code "83") (name "unconnected-(JP1-Pad44)") (class "Default")
      (node (ref "JP1") (pin "44") (pinfunction "44_44") (pintype "passive"))
    )
    (net (code "84") (name "unconnected-(JP1-Pad45)") (class "Default")
      (node (ref "JP1") (pin "45") (pinfunction "45_45") (pintype "passive"))
    )
    (net (code "85") (name "unconnected-(JP1-Pad46)") (class "Default")
      (node (ref "JP1") (pin "46") (pinfunction "46_46") (pintype "passive"))
    )
    (net (code "86") (name "unconnected-(JP2-Pad1)") (class "Default")
      (node (ref "JP2") (pin "1") (pinfunction "1_1") (pintype "passive"))
    )
    (net (code "87") (name "unconnected-(JP2-Pad3)") (class "Default")
      (node (ref "JP2") (pin "3") (pinfunction "3_3") (pintype "passive"))
    )
    (net (code "88") (name "unconnected-(JP2-Pad4)") (class "Default")
      (node (ref "JP2") (pin "4") (pinfunction "4_4") (pintype "passive"))
    )
    (net (code "89") (name "unconnected-(JP2-Pad5)") (class "Default")
      (node (ref "JP2") (pin "5") (pinfunction "5_5") (pintype "passive"))
    )
    (net (code "90") (name "unconnected-(JP2-Pad6)") (class "Default")
      (node (ref "JP2") (pin "6") (pinfunction "6_6") (pintype "passive"))
    )
    (net (code "91") (name "unconnected-(JP2-Pad7)") (class "Default")
      (node (ref "JP2") (pin "7") (pinfunction "7_7") (pintype "passive"))
    )
    (net (code "92") (name "unconnected-(JP2-Pad8)") (class "Default")
      (node (ref "JP2") (pin "8") (pinfunction "8_8") (pintype "passive"))
    )
    (net (code "93") (name "unconnected-(JP2-Pad9)") (class "Default")
      (node (ref "JP2") (pin "9") (pinfunction "9_9") (pintype "passive"))
    )
    (net (code "94") (name "unconnected-(JP2-Pad10)") (class "Default")
      (node (ref "JP2") (pin "10") (pinfunction "10_10") (pintype "passive"))
    )
    (net (code "95") (name "unconnected-(JP2-Pad11)") (class "Default")
      (node (ref "JP2") (pin "11") (pinfunction "11_11") (pintype "passive"))
    )
    (net (code "96") (name "unconnected-(JP2-Pad12)") (class "Default")
      (node (ref "JP2") (pin "12") (pinfunction "12_12") (pintype "passive"))
    )
    (net (code "97") (name "unconnected-(JP2-Pad13)") (class "Default")
      (node (ref "JP2") (pin "13") (pinfunction "13_13") (pintype "passive"))
    )
    (net (code "98") (name "unconnected-(JP2-Pad14)") (class "Default")
      (node (ref "JP2") (pin "14") (pinfunction "14_14") (pintype "passive"))
    )
    (net (code "99") (name "unconnected-(JP2-Pad15)") (class "Default")
      (node (ref "JP2") (pin "15") (pinfunction "15_15") (pintype "passive"))
    )
    (net (code "100") (name "unconnected-(JP2-Pad16)") (class "Default")
      (node (ref "JP2") (pin "16") (pinfunction "16_16") (pintype "passive"))
    )
    (net (code "101") (name "unconnected-(JP2-Pad17)") (class "Default")
      (node (ref "JP2") (pin "17") (pinfunction "17_17") (pintype "passive"))
    )
    (net (code "102") (name "unconnected-(JP2-Pad18)") (class "Default")
      (node (ref "JP2") (pin "18") (pinfunction "18_18") (pintype "passive"))
    )
    (net (code "103") (name "unconnected-(JP2-Pad19)") (class "Default")
      (node (ref "JP2") (pin "19") (pinfunction "19_19") (pintype "passive"))
    )
    (net (code "104") (name "unconnected-(JP2-Pad21)") (class "Default")
      (node (ref "JP2") (pin "21") (pinfunction "21_21") (pintype "passive"))
    )
    (net (code "105") (name "unconnected-(JP2-Pad22)") (class "Default")
      (node (ref "JP2") (pin "22") (pinfunction "22_22") (pintype "passive"))
    )
    (net (code "106") (name "unconnected-(JP2-Pad23)") (class "Default")
      (node (ref "JP2") (pin "23") (pinfunction "23_23") (pintype "passive"))
    )
    (net (code "107") (name "unconnected-(JP2-Pad24)") (class "Default")
      (node (ref "JP2") (pin "24") (pinfunction "24_24") (pintype "passive"))
    )
    (net (code "108") (name "unconnected-(JP2-Pad25)") (class "Default")
      (node (ref "JP2") (pin "25") (pinfunction "25_25") (pintype "passive"))
    )
    (net (code "109") (name "unconnected-(JP2-Pad26)") (class "Default")
      (node (ref "JP2") (pin "26") (pinfunction "26_26") (pintype "passive"))
    )
    (net (code "110") (name "unconnected-(JP2-Pad27)") (class "Default")
      (node (ref "JP2") (pin "27") (pinfunction "27_27") (pintype "passive"))
    )
    (net (code "111") (name "unconnected-(JP2-Pad28)") (class "Default")
      (node (ref "JP2") (pin "28") (pinfunction "28_28") (pintype "passive"))
    )
    (net (code "112") (name "unconnected-(JP2-Pad29)") (class "Default")
      (node (ref "JP2") (pin "29") (pinfunction "29_29") (pintype "passive"))
    )
    (net (code "113") (name "unconnected-(JP2-Pad30)") (class "Default")
      (node (ref "JP2") (pin "30") (pinfunction "30_30") (pintype "passive"))
    )
    (net (code "114") (name "unconnected-(JP2-Pad31)") (class "Default")
      (node (ref "JP2") (pin "31") (pinfunction "31_31") (pintype "passive"))
    )
    (net (code "115") (name "unconnected-(JP2-Pad32)") (class "Default")
      (node (ref "JP2") (pin "32") (pinfunction "32_32") (pintype "passive"))
    )
    (net (code "116") (name "unconnected-(JP2-Pad34)") (class "Default")
      (node (ref "JP2") (pin "34") (pinfunction "34_34") (pintype "passive"))
    )
    (net (code "117") (name "unconnected-(JP2-Pad37)") (class "Default")
      (node (ref "JP2") (pin "37") (pinfunction "37_37") (pintype "passive"))
    )
    (net (code "118") (name "unconnected-(JP2-Pad38)") (class "Default")
      (node (ref "JP2") (pin "38") (pinfunction "38_38") (pintype "passive"))
    )
    (net (code "119") (name "unconnected-(JP2-Pad39)") (class "Default")
      (node (ref "JP2") (pin "39") (pinfunction "39_39") (pintype "passive"))
    )
    (net (code "120") (name "unconnected-(JP2-Pad40)") (class "Default")
      (node (ref "JP2") (pin "40") (pinfunction "40_40") (pintype "passive"))
    )
    (net (code "121") (name "unconnected-(JP2-Pad41)") (class "Default")
      (node (ref "JP2") (pin "41") (pinfunction "41_41") (pintype "passive"))
    )
    (net (code "122") (name "unconnected-(JP2-Pad42)") (class "Default")
      (node (ref "JP2") (pin "42") (pinfunction "42_42") (pintype "passive"))
    )
    (net (code "123") (name "unconnected-(JP2-Pad43)") (class "Default")
      (node (ref "JP2") (pin "43") (pinfunction "43_43") (pintype "passive"))
    )
    (net (code "124") (name "unconnected-(JP2-Pad44)") (class "Default")
      (node (ref "JP2") (pin "44") (pinfunction "44_44") (pintype "passive"))
    )
    (net (code "125") (name "unconnected-(JP2-Pad45)") (class "Default")
      (node (ref "JP2") (pin "45") (pinfunction "45_45") (pintype "passive"))
    )
    (net (code "126") (name "unconnected-(JP2-Pad46)") (class "Default")
      (node (ref "JP2") (pin "46") (pinfunction "46_46") (pintype "passive"))
    )
    (net (code "127") (name "unconnected-(JP2-Pad48)") (class "Default")
      (node (ref "JP2") (pin "48") (pinfunction "48_48") (pintype "passive"))
    )
    (net (code "128") (name "unconnected-(JP2-Pad49)") (class "Default")
      (node (ref "JP2") (pin "49") (pinfunction "49_49") (pintype "passive"))
    )
    (net (code "129") (name "unconnected-(JP2-Pad50)") (class "Default")
      (node (ref "JP2") (pin "50") (pinfunction "50_50") (pintype "passive"))
    )
  )
)
